# Power.net
KiCad netlist of a schematic drawn in Altium Designer
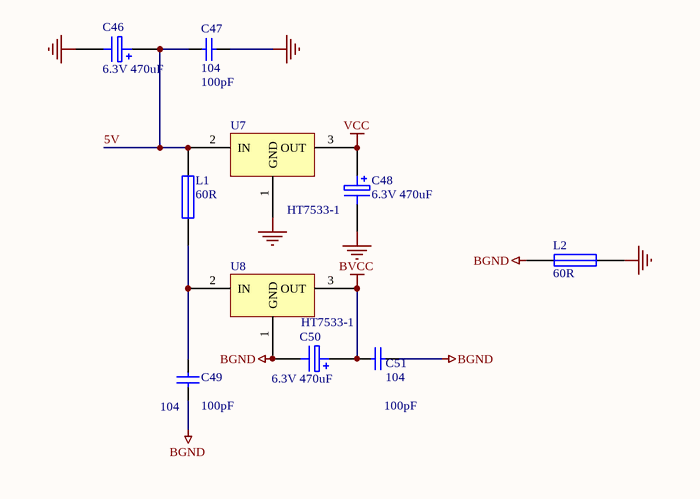
[diagram p0: Power.SchDoc]

(export (version "E")
  (design (tool "Eeschema 10.0.6"))
  (components
    (comp (ref "C46")
      (value "6.3V 470uF")
      (footprint "CC5.05.4")
      (description "Electrolytic Capacitor")
      (libsource (lib "Extra_Board_Mini") (part "ELECTRO1"))
    )
    (comp (ref "C47")
      (value "104")
      (footprint "0603C")
      (description "Capacitor")
      (fields (field (name "ALTIUM_VALUE") "100pF") (field (name "PUBLISHER") "Altium Limited"))
      (libsource (lib "Extra_Board_Mini") (part "Cap"))
    )
    (comp (ref "C48")
      (value "6.3V 470uF")
      (footprint "CC5.05.4")
      (description "Electrolytic Capacitor")
      (libsource (lib "Extra_Board_Mini") (part "ELECTRO1"))
    )
    (comp (ref "C49")
      (value "104")
      (footprint "0603C")
      (description "Capacitor")
      (fields (field (name "ALTIUM_VALUE") "100pF") (field (name "PUBLISHER") "Altium Limited"))
      (libsource (lib "Extra_Board_Mini") (part "Cap"))
    )
    (comp (ref "C50")
      (value "6.3V 470uF")
      (footprint "CC5.05.4")
      (description "Electrolytic Capacitor")
      (libsource (lib "Extra_Board_Mini") (part "ELECTRO1"))
    )
    (comp (ref "C51")
      (value "104")
      (footprint "0603C")
      (description "Capacitor")
      (fields (field (name "ALTIUM_VALUE") "100pF") (field (name "PUBLISHER") "Altium Limited"))
      (libsource (lib "Extra_Board_Mini") (part "Cap"))
    )
    (comp (ref "L1")
      (value "60R")
      (footprint "0603")
      (description "Fuse")
      (libsource (lib "Extra_Board_Mini") (part "FUSE1"))
    )
    (comp (ref "L2")
      (value "60R")
      (footprint "0603")
      (description "Fuse")
      (libsource (lib "Extra_Board_Mini") (part "FUSE1"))
    )
    (comp (ref "U7")
      (value "HT7533-1")
      (footprint "SOT89_M")
      (libsource (lib "Extra_Board_Mini") (part "HT7533-1"))
    )
    (comp (ref "U8")
      (value "HT7533-1")
      (footprint "SOT89_M")
      (libsource (lib "Extra_Board_Mini") (part "HT7533-1"))
    )
  )
  (nets
    (net (code "1") (name "/5V") (class "Default")
      (node (ref "C46") (pin "1") (pinfunction "1_1") (pintype "passive"))
      (node (ref "C47") (pin "2") (pinfunction "2_2") (pintype "passive"))
      (node (ref "L1") (pin "1") (pinfunction "1_1") (pintype "passive"))
      (node (ref "U7") (pin "2") (pinfunction "IN_2") (pintype "passive"))
    )
    (net (code "2") (name "BGND") (class "Default")
      (node (ref "C49") (pin "2") (pinfunction "2_2") (pintype "passive"))
      (node (ref "C50") (pin "2") (pinfunction "2_2") (pintype "passive"))
      (node (ref "C51") (pin "1") (pinfunction "1_1") (pintype "passive"))
      (node (ref "L2") (pin "1") (pinfunction "1_1") (pintype "passive"))
      (node (ref "U8") (pin "1") (pinfunction "GND_1") (pintype "passive"))
    )
    (net (code "3") (name "BVCC") (class "Default")
      (node (ref "C50") (pin "1") (pinfunction "1_1") (pintype "passive"))
      (node (ref "C51") (pin "2") (pinfunction "2_2") (pintype "passive"))
      (node (ref "U8") (pin "3") (pinfunction "OUT_3") (pintype "passive"))
    )
    (net (code "4") (name "GND") (class "Default")
      (node (ref "C46") (pin "2") (pinfunction "2_2") (pintype "passive"))
      (node (ref "C47") (pin "1") (pinfunction "1_1") (pintype "passive"))
      (node (ref "C48") (pin "2") (pinfunction "2_2") (pintype "passive"))
      (node (ref "L2") (pin "2") (pinfunction "2_2") (pintype "passive"))
      (node (ref "U7") (pin "1") (pinfunction "GND_1") (pintype "passive"))
    )
    (net (code "5") (name "Net-(U8-IN)") (class "Default")
      (node (ref "C49") (pin "1") (pinfunction "1_1") (pintype "passive"))
      (node (ref "L1") (pin "2") (pinfunction "2_2") (pintype "passive"))
      (node (ref "U8") (pin "2") (pinfunction "IN_2") (pintype "passive"))
    )
    (net (code "6") (name "VCC") (class "Default")
      (node (ref "C48") (pin "1") (pinfunction "1_1") (pintype "passive"))
      (node (ref "U7") (pin "3") (pinfunction "OUT_3") (pintype "passive"))
    )
  )
)
